# controller.net
KiCad netlist of a schematic drawn in EAGLE
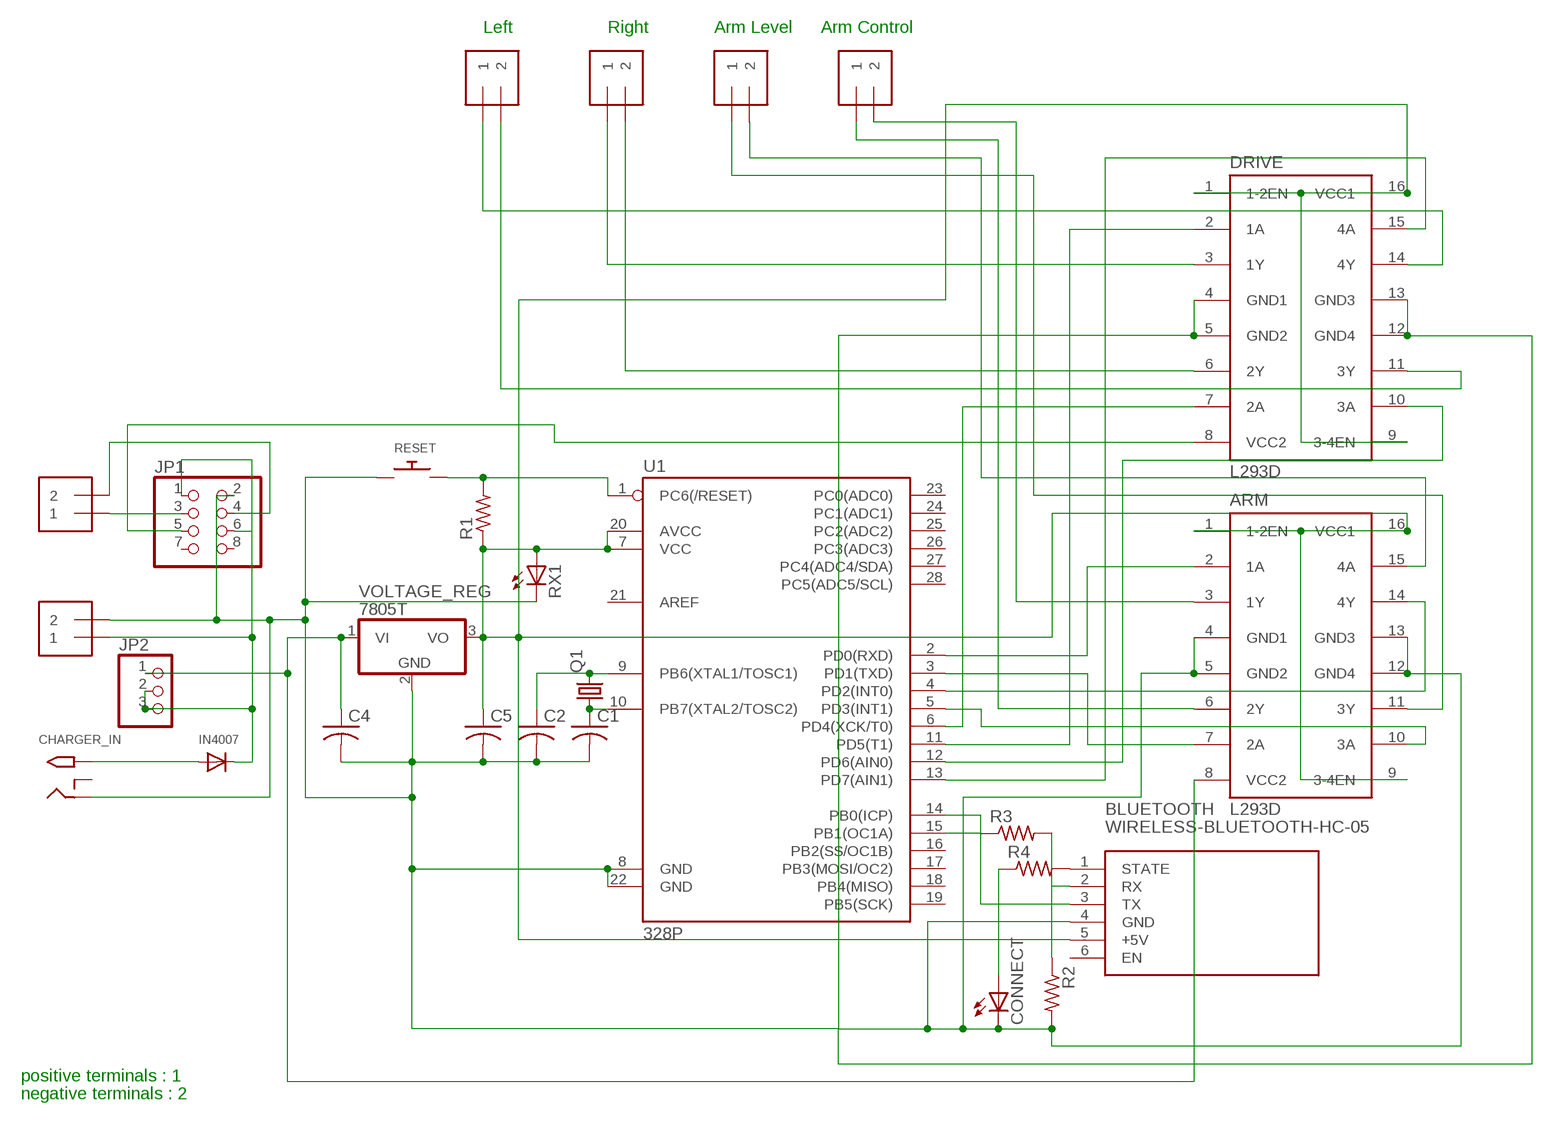
[diagram p0: schematic, sheet 1]

(export (version "E")
  (design (tool "Eeschema 10.0.6"))
  (components
    (comp (ref "ARM")
      (value "L293D")
      (footprint "eagle-import:DIL16")
      (libsource (lib "eagle-import") (part "L293D"))
    )
    (comp (ref "ARM_LEVEL")
      (value "1X2-3.5MM")
      (footprint "eagle-import:1X2-3.5MM")
      (libsource (lib "eagle-import") (part "1X2-3.5MM"))
    )
    (comp (ref "BATTERY_1")
      (value "1X2-3.5MM")
      (footprint "eagle-import:1X2-3.5MM")
      (libsource (lib "eagle-import") (part "1X2-3.5MM"))
    )
    (comp (ref "BATTERY_2")
      (value "1X2-3.5MM")
      (footprint "eagle-import:1X2-3.5MM")
      (libsource (lib "eagle-import") (part "1X2-3.5MM"))
    )
    (comp (ref "BLUETOOTH")
      (value "WIRELESS-BLUETOOTH-HC-05")
      (footprint "eagle-import:WIRELESS-BLUETOOTH-HC-05")
      (libsource (lib "eagle-import") (part "WIRELESS-BLUETOOTH-HC-05"))
    )
    (comp (ref "C1")
      (value "C-US025-025X050")
      (footprint "eagle-import:C025-025X050")
      (libsource (lib "eagle-import") (part "C-US025-025X050"))
    )
    (comp (ref "C2")
      (value "C-US025-025X050")
      (footprint "eagle-import:C025-025X050")
      (libsource (lib "eagle-import") (part "C-US025-025X050"))
    )
    (comp (ref "C4")
      (value "C-US050-030X075")
      (footprint "eagle-import:C050-030X075")
      (libsource (lib "eagle-import") (part "C-US050-030X075"))
    )
    (comp (ref "C5")
      (value "C-US050-030X075")
      (footprint "eagle-import:C050-030X075")
      (libsource (lib "eagle-import") (part "C-US050-030X075"))
    )
    (comp (ref "CHARGER_IN")
      (value "2.1MMJACKTHM")
      (footprint "eagle-import:PJ-102A")
      (libsource (lib "eagle-import") (part "2.1MMJACKTHM"))
    )
    (comp (ref "CONNECT")
      (value "LED5MM")
      (footprint "eagle-import:LED5MM")
      (libsource (lib "eagle-import") (part "LED5MM"))
    )
    (comp (ref "DRIVE")
      (value "L293D")
      (footprint "eagle-import:DIL16")
      (libsource (lib "eagle-import") (part "L293D"))
    )
    (comp (ref "GRIPPER")
      (value "1X2-3.5MM")
      (footprint "eagle-import:1X2-3.5MM")
      (libsource (lib "eagle-import") (part "1X2-3.5MM"))
    )
    (comp (ref "IN4007")
      (value "DIODEDO-1N4148")
      (footprint "eagle-import:DO-1N4148")
      (libsource (lib "eagle-import") (part "DIODEDO-1N4148"))
    )
    (comp (ref "JP1")
      (value "PINHD-2X4")
      (footprint "eagle-import:2X04")
      (libsource (lib "eagle-import") (part "PINHD-2X4"))
    )
    (comp (ref "JP2")
      (value "PINHD-1X3")
      (footprint "eagle-import:1X03")
      (libsource (lib "eagle-import") (part "PINHD-1X3"))
    )
    (comp (ref "LEFT")
      (value "1X2-3.5MM")
      (footprint "eagle-import:1X2-3.5MM")
      (libsource (lib "eagle-import") (part "1X2-3.5MM"))
    )
    (comp (ref "Q1")
      (value "CRYSTALHC49S")
      (footprint "eagle-import:HC49_S")
      (libsource (lib "eagle-import") (part "CRYSTALHC49S"))
    )
    (comp (ref "R1")
      (value "R-US_0204/7")
      (footprint "eagle-import:0204_7")
      (libsource (lib "eagle-import") (part "R-US_0204/7"))
    )
    (comp (ref "R2")
      (value "R-US_0204/7")
      (footprint "eagle-import:0204_7")
      (libsource (lib "eagle-import") (part "R-US_0204/7"))
    )
    (comp (ref "R3")
      (value "R-US_0204/7")
      (footprint "eagle-import:0204_7")
      (libsource (lib "eagle-import") (part "R-US_0204/7"))
    )
    (comp (ref "R4")
      (value "R-US_0204/7")
      (footprint "eagle-import:0204_7")
      (libsource (lib "eagle-import") (part "R-US_0204/7"))
    )
    (comp (ref "RESET")
      (value "SWITCH_PUSHBUTTONSOFTTOUCHSMD_SJ")
      (footprint "eagle-import:PUSHBUTTON_SMD_SJ")
      (libsource (lib "eagle-import") (part "SWITCH_PUSHBUTTONSOFTTOUCHSMD_SJ"))
    )
    (comp (ref "RIGHT")
      (value "1X2-3.5MM")
      (footprint "eagle-import:1X2-3.5MM")
      (libsource (lib "eagle-import") (part "1X2-3.5MM"))
    )
    (comp (ref "RX1")
      (value "LED5MM")
      (footprint "eagle-import:LED5MM")
      (libsource (lib "eagle-import") (part "LED5MM"))
    )
    (comp (ref "U1")
      (value "328P")
      (footprint "eagle-import:DIP28")
      (libsource (lib "eagle-import") (part "ATMEGA328P_PDIP"))
    )
    (comp (ref "VOLTAGE_REG")
      (value "7805T")
      (footprint "eagle-import:TO220H")
      (libsource (lib "eagle-import") (part "78T05"))
    )
  )
  (nets
    (net (code "1") (name "Net-(ARM-1-2EN)") (class "Default")
      (node (ref "ARM") (pin "1") (pinfunction "1-2EN_1") (pintype "input"))
      (node (ref "ARM") (pin "16") (pinfunction "VCC1_16") (pintype "power_in"))
      (node (ref "ARM") (pin "9") (pinfunction "3-4EN_9") (pintype "input"))
      (node (ref "BLUETOOTH") (pin "5") (pinfunction "+5V_5") (pintype "power_in"))
      (node (ref "C5") (pin "1") (pinfunction "1_1") (pintype "passive"))
      (node (ref "DRIVE") (pin "1") (pinfunction "1-2EN_1") (pintype "input"))
      (node (ref "DRIVE") (pin "16") (pinfunction "VCC1_16") (pintype "power_in"))
      (node (ref "DRIVE") (pin "9") (pinfunction "3-4EN_9") (pintype "input"))
      (node (ref "R1") (pin "1") (pinfunction "1_1") (pintype "passive"))
      (node (ref "RX1") (pin "A") (pinfunction "A_A") (pintype "passive"))
      (node (ref "U1") (pin "20") (pinfunction "AVCC_20") (pintype "bidirectional"))
      (node (ref "U1") (pin "7") (pinfunction "VCC_7") (pintype "bidirectional"))
      (node (ref "VOLTAGE_REG") (pin "3") (pinfunction "VO_3") (pintype "passive"))
    )
    (net (code "2") (name "Net-(ARM-1A)") (class "Default")
      (node (ref "ARM") (pin "2") (pinfunction "1A_2") (pintype "input"))
      (node (ref "U1") (pin "2") (pinfunction "PD0(RXD)_2") (pintype "bidirectional"))
    )
    (net (code "3") (name "Net-(ARM-1Y)") (class "Default")
      (node (ref "ARM") (pin "3") (pinfunction "1Y_3") (pintype "output"))
      (node (ref "GRIPPER") (pin "2") (pinfunction "2_2") (pintype "passive"))
    )
    (net (code "4") (name "Net-(ARM-2A)") (class "Default")
      (node (ref "ARM") (pin "7") (pinfunction "2A_7") (pintype "input"))
      (node (ref "U1") (pin "3") (pinfunction "PD1(TXD)_3") (pintype "bidirectional"))
    )
    (net (code "5") (name "Net-(ARM-2Y)") (class "Default")
      (node (ref "ARM") (pin "6") (pinfunction "2Y_6") (pintype "output"))
      (node (ref "GRIPPER") (pin "1") (pinfunction "1_1") (pintype "passive"))
    )
    (net (code "6") (name "Net-(ARM-3A)") (class "Default")
      (node (ref "ARM") (pin "10") (pinfunction "3A_10") (pintype "input"))
      (node (ref "U1") (pin "5") (pinfunction "PD3(INT1)_5") (pintype "bidirectional"))
    )
    (net (code "7") (name "Net-(ARM-3Y)") (class "Default")
      (node (ref "ARM") (pin "11") (pinfunction "3Y_11") (pintype "output"))
      (node (ref "ARM_LEVEL") (pin "1") (pinfunction "1_1") (pintype "passive"))
    )
    (net (code "8") (name "Net-(ARM-4A)") (class "Default")
      (node (ref "ARM") (pin "15") (pinfunction "4A_15") (pintype "input"))
      (node (ref "ARM_LEVEL") (pin "2") (pinfunction "2_2") (pintype "passive"))
    )
    (net (code "9") (name "Net-(ARM-4Y)") (class "Default")
      (node (ref "ARM") (pin "14") (pinfunction "4Y_14") (pintype "output"))
      (node (ref "U1") (pin "4") (pinfunction "PD2(INT0)_4") (pintype "bidirectional"))
    )
    (net (code "10") (name "Net-(ARM-GND1)") (class "Default")
      (node (ref "ARM") (pin "12") (pinfunction "GND4_12") (pintype "power_in"))
      (node (ref "ARM") (pin "13") (pinfunction "GND3_13") (pintype "power_in"))
      (node (ref "ARM") (pin "4") (pinfunction "GND1_4") (pintype "power_in"))
      (node (ref "ARM") (pin "5") (pinfunction "GND2_5") (pintype "power_in"))
      (node (ref "BATTERY_2") (pin "2") (pinfunction "2_2") (pintype "passive"))
      (node (ref "BLUETOOTH") (pin "4") (pinfunction "GND_4") (pintype "power_in"))
      (node (ref "C1") (pin "2") (pinfunction "2_2") (pintype "passive"))
      (node (ref "C2") (pin "2") (pinfunction "2_2") (pintype "passive"))
      (node (ref "C4") (pin "2") (pinfunction "2_2") (pintype "passive"))
      (node (ref "C5") (pin "2") (pinfunction "2_2") (pintype "passive"))
      (node (ref "CHARGER_IN") (pin "RING") (pinfunction "RING_RING") (pintype "bidirectional"))
      (node (ref "CONNECT") (pin "K") (pinfunction "C_K") (pintype "passive"))
      (node (ref "DRIVE") (pin "12") (pinfunction "GND4_12") (pintype "power_in"))
      (node (ref "DRIVE") (pin "13") (pinfunction "GND3_13") (pintype "power_in"))
      (node (ref "DRIVE") (pin "4") (pinfunction "GND1_4") (pintype "power_in"))
      (node (ref "DRIVE") (pin "5") (pinfunction "GND2_5") (pintype "power_in"))
      (node (ref "JP1") (pin "2") (pinfunction "2_2") (pintype "passive"))
      (node (ref "R2") (pin "2") (pinfunction "2_2") (pintype "passive"))
      (node (ref "RESET") (pin "P$1") (pinfunction "P$1_P$1") (pintype "passive"))
      (node (ref "RX1") (pin "K") (pinfunction "C_K") (pintype "passive"))
      (node (ref "U1") (pin "22") (pinfunction "GND_22") (pintype "bidirectional"))
      (node (ref "U1") (pin "8") (pinfunction "GND_8") (pintype "bidirectional"))
      (node (ref "VOLTAGE_REG") (pin "2") (pinfunction "GND_2") (pintype "passive"))
    )
    (net (code "11") (name "Net-(ARM-VCC2)") (class "Default")
      (node (ref "ARM") (pin "8") (pinfunction "VCC2_8") (pintype "power_in"))
      (node (ref "C4") (pin "1") (pinfunction "1_1") (pintype "passive"))
      (node (ref "JP2") (pin "1") (pinfunction "1_1") (pintype "passive"))
      (node (ref "VOLTAGE_REG") (pin "1") (pinfunction "VI_1") (pintype "input"))
    )
    (net (code "12") (name "Net-(BATTERY_1-Pad1)") (class "Default")
      (node (ref "BATTERY_1") (pin "1") (pinfunction "1_1") (pintype "passive"))
      (node (ref "JP1") (pin "3") (pinfunction "3_3") (pintype "passive"))
    )
    (net (code "13") (name "Net-(BATTERY_1-Pad2)") (class "Default")
      (node (ref "BATTERY_1") (pin "2") (pinfunction "2_2") (pintype "passive"))
      (node (ref "JP1") (pin "4") (pinfunction "4_4") (pintype "passive"))
    )
    (net (code "14") (name "Net-(BATTERY_2-Pad1)") (class "Default")
      (node (ref "BATTERY_2") (pin "1") (pinfunction "1_1") (pintype "passive"))
      (node (ref "IN4007") (pin "C") (pinfunction "C_C") (pintype "passive"))
      (node (ref "JP1") (pin "1") (pinfunction "1_1") (pintype "passive"))
      (node (ref "JP1") (pin "6") (pinfunction "6_6") (pintype "passive"))
      (node (ref "JP2") (pin "2") (pinfunction "2_2") (pintype "passive"))
      (node (ref "JP2") (pin "3") (pinfunction "3_3") (pintype "passive"))
    )
    (net (code "15") (name "Net-(BLUETOOTH-RX)") (class "Default")
      (node (ref "BLUETOOTH") (pin "2") (pinfunction "RX_2") (pintype "bidirectional"))
      (node (ref "R2") (pin "1") (pinfunction "1_1") (pintype "passive"))
      (node (ref "R3") (pin "2") (pinfunction "2_2") (pintype "passive"))
    )
    (net (code "16") (name "Net-(BLUETOOTH-STATE)") (class "Default")
      (node (ref "BLUETOOTH") (pin "1") (pinfunction "STATE_1") (pintype "bidirectional"))
      (node (ref "R4") (pin "2") (pinfunction "2_2") (pintype "passive"))
    )
    (net (code "17") (name "Net-(BLUETOOTH-TX)") (class "Default")
      (node (ref "BLUETOOTH") (pin "3") (pinfunction "TX_3") (pintype "bidirectional"))
      (node (ref "U1") (pin "14") (pinfunction "PB0(ICP)_14") (pintype "bidirectional"))
    )
    (net (code "18") (name "Net-(CHARGER_IN-PadTIP)") (class "Default")
      (node (ref "CHARGER_IN") (pin "TIP") (pinfunction "TIP_TIP") (pintype "bidirectional"))
      (node (ref "IN4007") (pin "A") (pinfunction "A_A") (pintype "passive"))
    )
    (net (code "19") (name "Net-(CONNECT-PadA)") (class "Default")
      (node (ref "CONNECT") (pin "A") (pinfunction "A_A") (pintype "passive"))
      (node (ref "R4") (pin "1") (pinfunction "1_1") (pintype "passive"))
    )
    (net (code "20") (name "Net-(DRIVE-1A)") (class "Default")
      (node (ref "DRIVE") (pin "2") (pinfunction "1A_2") (pintype "input"))
      (node (ref "U1") (pin "11") (pinfunction "PD5(T1)_11") (pintype "bidirectional"))
    )
    (net (code "21") (name "Net-(DRIVE-1Y)") (class "Default")
      (node (ref "DRIVE") (pin "3") (pinfunction "1Y_3") (pintype "output"))
      (node (ref "RIGHT") (pin "1") (pinfunction "1_1") (pintype "passive"))
    )
    (net (code "22") (name "Net-(DRIVE-2A)") (class "Default")
      (node (ref "DRIVE") (pin "7") (pinfunction "2A_7") (pintype "input"))
      (node (ref "U1") (pin "6") (pinfunction "PD4(XCK/T0)_6") (pintype "bidirectional"))
    )
    (net (code "23") (name "Net-(DRIVE-2Y)") (class "Default")
      (node (ref "DRIVE") (pin "6") (pinfunction "2Y_6") (pintype "output"))
      (node (ref "RIGHT") (pin "2") (pinfunction "2_2") (pintype "passive"))
    )
    (net (code "24") (name "Net-(DRIVE-3A)") (class "Default")
      (node (ref "DRIVE") (pin "10") (pinfunction "3A_10") (pintype "input"))
      (node (ref "U1") (pin "12") (pinfunction "PD6(AIN0)_12") (pintype "bidirectional"))
    )
    (net (code "25") (name "Net-(DRIVE-3Y)") (class "Default")
      (node (ref "DRIVE") (pin "11") (pinfunction "3Y_11") (pintype "output"))
      (node (ref "LEFT") (pin "2") (pinfunction "2_2") (pintype "passive"))
    )
    (net (code "26") (name "Net-(DRIVE-4A)") (class "Default")
      (node (ref "DRIVE") (pin "15") (pinfunction "4A_15") (pintype "input"))
      (node (ref "U1") (pin "13") (pinfunction "PD7(AIN1)_13") (pintype "bidirectional"))
    )
    (net (code "27") (name "Net-(DRIVE-4Y)") (class "Default")
      (node (ref "DRIVE") (pin "14") (pinfunction "4Y_14") (pintype "output"))
      (node (ref "LEFT") (pin "1") (pinfunction "1_1") (pintype "passive"))
    )
    (net (code "28") (name "Net-(DRIVE-VCC2)") (class "Default")
      (node (ref "DRIVE") (pin "8") (pinfunction "VCC2_8") (pintype "power_in"))
      (node (ref "JP1") (pin "5") (pinfunction "5_5") (pintype "passive"))
    )
    (net (code "29") (name "Net-(U1-PB1(OC1A))") (class "Default")
      (node (ref "R3") (pin "1") (pinfunction "1_1") (pintype "passive"))
      (node (ref "U1") (pin "15") (pinfunction "PB1(OC1A)_15") (pintype "bidirectional"))
    )
    (net (code "30") (name "Net-(U1-PB6(XTAL1{slash}TOSC1))") (class "Default")
      (node (ref "C2") (pin "1") (pinfunction "1_1") (pintype "passive"))
      (node (ref "Q1") (pin "2") (pinfunction "2_2") (pintype "passive"))
      (node (ref "U1") (pin "9") (pinfunction "PB6(XTAL1/TOSC1)_9") (pintype "bidirectional"))
    )
    (net (code "31") (name "Net-(U1-PB7(XTAL2{slash}TOSC2))") (class "Default")
      (node (ref "C1") (pin "1") (pinfunction "1_1") (pintype "passive"))
      (node (ref "Q1") (pin "1") (pinfunction "1_1") (pintype "passive"))
      (node (ref "U1") (pin "10") (pinfunction "PB7(XTAL2/TOSC2)_10") (pintype "bidirectional"))
    )
    (net (code "32") (name "Net-(U1-PC6({slash}RESET))") (class "Default")
      (node (ref "R1") (pin "2") (pinfunction "2_2") (pintype "passive"))
      (node (ref "RESET") (pin "P$2") (pinfunction "P$2_P$2") (pintype "passive"))
      (node (ref "U1") (pin "1") (pinfunction "PC6(/RESET)_1") (pintype "bidirectional"))
    )
    (net (code "33") (name "unconnected-(BLUETOOTH-EN-Pad6)") (class "Default")
      (node (ref "BLUETOOTH") (pin "6") (pinfunction "EN_6") (pintype "bidirectional"))
    )
    (net (code "34") (name "unconnected-(CHARGER_IN-PadRING_SW)") (class "Default")
      (node (ref "CHARGER_IN") (pin "RING_SW") (pinfunction "RING_SW_RING_SW") (pintype "bidirectional"))
    )
    (net (code "35") (name "unconnected-(JP1-Pad7)") (class "Default")
      (node (ref "JP1") (pin "7") (pinfunction "7_7") (pintype "passive"))
    )
    (net (code "36") (name "unconnected-(JP1-Pad8)") (class "Default")
      (node (ref "JP1") (pin "8") (pinfunction "8_8") (pintype "passive"))
    )
    (net (code "37") (name "unconnected-(U1-AREF-Pad21)") (class "Default")
      (node (ref "U1") (pin "21") (pinfunction "AREF_21") (pintype "bidirectional"))
    )
    (net (code "38") (name "unconnected-(U1-PB2(SS{slash}OC1B)-Pad16)") (class "Default")
      (node (ref "U1") (pin "16") (pinfunction "PB2(SS/OC1B)_16") (pintype "bidirectional"))
    )
    (net (code "39") (name "unconnected-(U1-PB3(MOSI{slash}OC2)-Pad17)") (class "Default")
      (node (ref "U1") (pin "17") (pinfunction "PB3(MOSI/OC2)_17") (pintype "bidirectional"))
    )
    (net (code "40") (name "unconnected-(U1-PB4(MISO)-Pad18)") (class "Default")
      (node (ref "U1") (pin "18") (pinfunction "PB4(MISO)_18") (pintype "bidirectional"))
    )
    (net (code "41") (name "unconnected-(U1-PB5(SCK)-Pad19)") (class "Default")
      (node (ref "U1") (pin "19") (pinfunction "PB5(SCK)_19") (pintype "bidirectional"))
    )
    (net (code "42") (name "unconnected-(U1-PC0(ADC0)-Pad23)") (class "Default")
      (node (ref "U1") (pin "23") (pinfunction "PC0(ADC0)_23") (pintype "bidirectional"))
    )
    (net (code "43") (name "unconnected-(U1-PC1(ADC1)-Pad24)") (class "Default")
      (node (ref "U1") (pin "24") (pinfunction "PC1(ADC1)_24") (pintype "bidirectional"))
    )
    (net (code "44") (name "unconnected-(U1-PC2(ADC2)-Pad25)") (class "Default")
      (node (ref "U1") (pin "25") (pinfunction "PC2(ADC2)_25") (pintype "bidirectional"))
    )
    (net (code "45") (name "unconnected-(U1-PC3(ADC3)-Pad26)") (class "Default")
      (node (ref "U1") (pin "26") (pinfunction "PC3(ADC3)_26") (pintype "bidirectional"))
    )
    (net (code "46") (name "unconnected-(U1-PC4(ADC4{slash}SDA)-Pad27)") (class "Default")
      (node (ref "U1") (pin "27") (pinfunction "PC4(ADC4/SDA)_27") (pintype "bidirectional"))
    )
    (net (code "47") (name "unconnected-(U1-PC5(ADC5{slash}SCL)-Pad28)") (class "Default")
      (node (ref "U1") (pin "28") (pinfunction "PC5(ADC5/SCL)_28") (pintype "bidirectional"))
    )
  )
)
